# MCU.net
KiCad netlist of a schematic drawn in Altium Designer
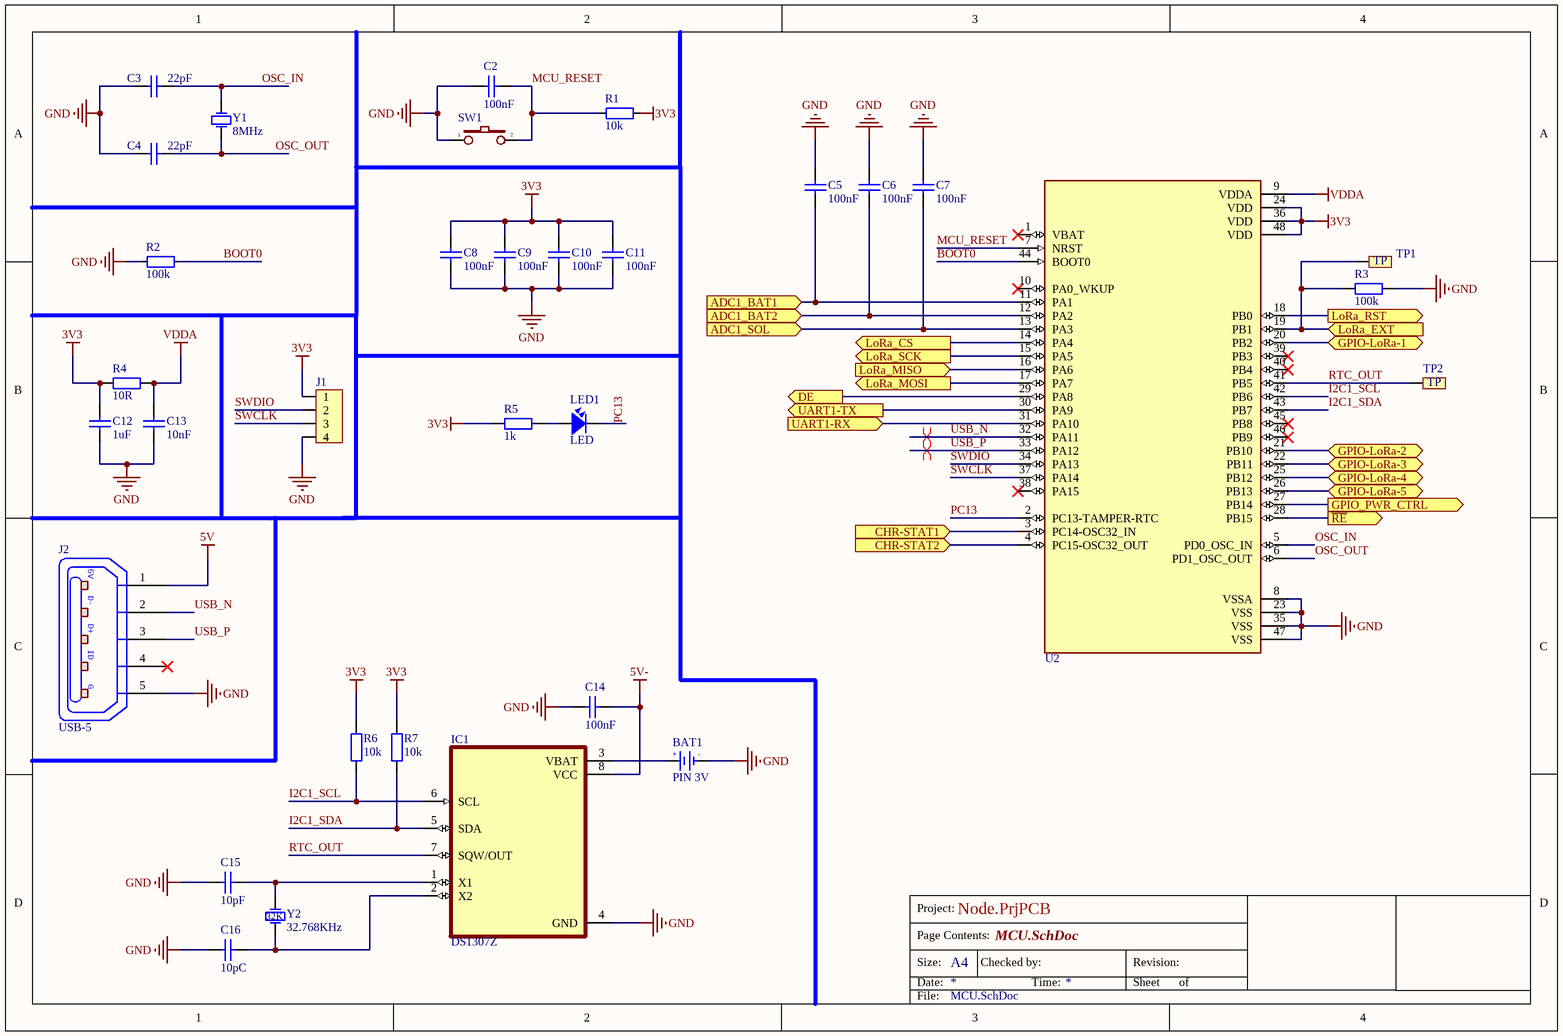
[diagram p0: MCU.SchDoc]

(export (version "E")
  (design (tool "Eeschema 10.0.6"))
  (components
    (comp (ref "BAT1")
      (value "PIN 3V")
      (footprint "CR1220 SMD")
      (description "Battery 3VDC")
      (libsource (lib "My Library") (part "PIN 3V"))
    )
    (comp (ref "C2")
      (value "100nF")
      (footprint "CAP_0805")
      (description "Capacitor")
      (fields (field (name "PUBLISHER") "Altium Limited"))
      (libsource (lib "My Library") (part "CapSMD"))
    )
    (comp (ref "C3")
      (value "22pF")
      (footprint "CAP_0805")
      (description "Capacitor")
      (fields (field (name "PUBLISHER") "Altium Limited"))
      (libsource (lib "My Library") (part "CapSMD"))
    )
    (comp (ref "C4")
      (value "22pF")
      (footprint "CAP_0805")
      (description "Capacitor")
      (fields (field (name "PUBLISHER") "Altium Limited"))
      (libsource (lib "My Library") (part "CapSMD"))
    )
    (comp (ref "C5")
      (value "100nF")
      (footprint "CAP_0805")
      (description "Capacitor")
      (fields (field (name "PUBLISHER") "Altium Limited"))
      (libsource (lib "My Library") (part "CapSMD"))
    )
    (comp (ref "C6")
      (value "100nF")
      (footprint "CAP_0805")
      (description "Capacitor")
      (fields (field (name "PUBLISHER") "Altium Limited"))
      (libsource (lib "My Library") (part "CapSMD"))
    )
    (comp (ref "C7")
      (value "100nF")
      (footprint "CAP_0805")
      (description "Capacitor")
      (fields (field (name "PUBLISHER") "Altium Limited"))
      (libsource (lib "My Library") (part "CapSMD"))
    )
    (comp (ref "C8")
      (value "100nF")
      (footprint "CAP_0805")
      (description "Capacitor")
      (fields (field (name "PUBLISHER") "Altium Limited"))
      (libsource (lib "My Library") (part "CapSMD"))
    )
    (comp (ref "C9")
      (value "100nF")
      (footprint "CAP_0805")
      (description "Capacitor")
      (fields (field (name "PUBLISHER") "Altium Limited"))
      (libsource (lib "My Library") (part "CapSMD"))
    )
    (comp (ref "C10")
      (value "100nF")
      (footprint "CAP_0805")
      (description "Capacitor")
      (fields (field (name "PUBLISHER") "Altium Limited"))
      (libsource (lib "My Library") (part "CapSMD"))
    )
    (comp (ref "C11")
      (value "100nF")
      (footprint "CAP_0805")
      (description "Capacitor")
      (fields (field (name "PUBLISHER") "Altium Limited"))
      (libsource (lib "My Library") (part "CapSMD"))
    )
    (comp (ref "C12")
      (value "1uF")
      (footprint "CAP_0805")
      (description "Capacitor")
      (fields (field (name "PUBLISHER") "Altium Limited"))
      (libsource (lib "My Library") (part "CapSMD"))
    )
    (comp (ref "C13")
      (value "10nF")
      (footprint "CAP_0805")
      (description "Capacitor")
      (fields (field (name "PUBLISHER") "Altium Limited"))
      (libsource (lib "My Library") (part "CapSMD"))
    )
    (comp (ref "C14")
      (value "100nF")
      (footprint "CAP_0805")
      (description "Capacitor")
      (fields (field (name "PUBLISHER") "Altium Limited"))
      (libsource (lib "My Library") (part "CapSMD"))
    )
    (comp (ref "C15")
      (value "10pF")
      (footprint "CAP_0805")
      (description "Capacitor")
      (fields (field (name "PUBLISHER") "Altium Limited"))
      (libsource (lib "My Library") (part "CapSMD"))
    )
    (comp (ref "C16")
      (value "10pC")
      (footprint "CAP_0805")
      (description "Capacitor")
      (fields (field (name "PUBLISHER") "Altium Limited"))
      (libsource (lib "My Library") (part "CapSMD"))
    )
    (comp (ref "IC1") (value "DS1307Z") (footprint "SOIC-8") (libsource (lib "My Library") (part "DS1307Z")))
    (comp (ref "J1")
      (value "ST_Link")
      (footprint "Jump_4p")
      (description "Header IDC, 4 x 1 Pin Vertical 2.54mm Pitch (Non-Boxed, Male)")
      (fields
        (field (name "MANUFACTURER") "Würth Elektronik eiSos GmbH")
        (field (name "PARTNO") "613002143121")
        (field (name "CREATED BY") "Karrer Zheng")
      )
      (libsource (lib "My Library") (part "Header4"))
    )
    (comp (ref "J2")
      (value "USB-5")
      (footprint "USB-M1")
      (fields
        (field (name "MANUFACTURER") "FCI")
        (field (name "MANUFACTURER PART NUMBER") "10118193-0001LF")
        (field (name ".CREATOR") "MM")
        (field (name ".CHECKED PCB") "RF")
        (field (name ".CHECKED SCH") "MM")
      )
      (libsource (lib "My Library") (part "USB-5"))
    )
    (comp (ref "LED1")
      (value "LED")
      (footprint "LED-0805-Red")
      (description "LED Single colour Green and Red")
      (libsource (lib "My Library") (part "LED"))
    )
    (comp (ref "R1")
      (value "10k")
      (footprint "RES-SMD-0805")
      (description "Resistor")
      (fields
        (field (name "MANUFACTURER") "Generic Components")
        (field (name "PUBLISHER") "Altium Hobart Technology Centre")
      )
      (libsource (lib "") (part "Resistor - SMD_1"))
    )
    (comp (ref "R2")
      (value "100k")
      (footprint "RES-SMD-0805")
      (description "Resistor")
      (fields
        (field (name "MANUFACTURER") "Generic Components")
        (field (name "PUBLISHER") "Altium Hobart Technology Centre")
      )
      (libsource (lib "") (part "Resistor - SMD_1"))
    )
    (comp (ref "R3")
      (value "100k")
      (footprint "RES-SMD-0805")
      (description "Resistor SMD")
      (fields
        (field (name "MANUFACTURER") "Generic Components")
        (field (name "PUBLISHER") "Altium Hobart Technology Centre")
      )
      (libsource (lib "My Library") (part "Resistor - SMD"))
    )
    (comp (ref "R4")
      (value "10R")
      (footprint "RES-SMD-0805")
      (description "Resistor SMD")
      (fields
        (field (name "MANUFACTURER") "Generic Components")
        (field (name "PUBLISHER") "Altium Hobart Technology Centre")
      )
      (libsource (lib "My Library") (part "Resistor - SMD"))
    )
    (comp (ref "R5")
      (value "1k")
      (footprint "RES-SMD-0805")
      (description "Resistor SMD")
      (fields
        (field (name "MANUFACTURER") "Generic Components")
        (field (name "PUBLISHER") "Altium Hobart Technology Centre")
      )
      (libsource (lib "My Library") (part "Resistor - SMD"))
    )
    (comp (ref "R6")
      (value "10k")
      (footprint "RES-SMD-0805")
      (description "Resistor SMD")
      (fields
        (field (name "MANUFACTURER") "Generic Components")
        (field (name "PUBLISHER") "Altium Hobart Technology Centre")
      )
      (libsource (lib "My Library") (part "Resistor - SMD"))
    )
    (comp (ref "R7")
      (value "10k")
      (footprint "RES-SMD-0805")
      (description "Resistor SMD")
      (fields
        (field (name "MANUFACTURER") "Generic Components")
        (field (name "PUBLISHER") "Altium Hobart Technology Centre")
      )
      (libsource (lib "My Library") (part "Resistor - SMD"))
    )
    (comp (ref "SW1")
      (value "SW")
      (footprint "SW 3x2x4")
      (description "Switch button 2 pin")
      (libsource (lib "My Library") (part "SW2"))
    )
    (comp (ref "TP1")
      (value "Test Point")
      (footprint "TP_SMD")
      (description "CONNECT 1")
      (libsource (lib "My Library") (part "TP"))
    )
    (comp (ref "TP2")
      (value "Test Point")
      (footprint "TP_SMD")
      (description "CONNECT 1")
      (libsource (lib "My Library") (part "TP"))
    )
    (comp (ref "U2")
      (value "STM32")
      (footprint "LQFP 48")
      (description "STM32 ARM-based 32-bit MCU with 64 Kbytes Flash, 64-pin LQFP, Industrial Temperature")
      (libsource (lib "Ven_lib") (part "STM32F103C8T6"))
    )
    (comp (ref "Y1")
      (value "8MHz")
      (footprint "XTAL")
      (description "Crystal Oscillator")
      (fields (field (name "PUBLISHER") "Altium Limited"))
      (libsource (lib "My Library") (part "XTAL"))
    )
    (comp (ref "Y2")
      (value "32.768KHz")
      (footprint "XTAL32K")
      (description "Crystal Oscillator")
      (fields (field (name "PUBLISHER") "Altium Limited"))
      (libsource (lib "My Library") (part "XTAL/32KHz"))
    )
  )
  (nets
    (net (code "1") (name "/ADC1_BAT1") (class "Default")
      (node (ref "C5") (pin "1") (pinfunction "1_1") (pintype "passive"))
      (node (ref "U2") (pin "11") (pinfunction "PA1_11") (pintype "bidirectional"))
    )
    (net (code "2") (name "/ADC1_BAT2") (class "Default")
      (node (ref "C6") (pin "1") (pinfunction "1_1") (pintype "passive"))
      (node (ref "U2") (pin "12") (pinfunction "PA2_12") (pintype "bidirectional"))
    )
    (net (code "3") (name "/ADC1_SOL") (class "Default")
      (node (ref "C7") (pin "1") (pinfunction "1_1") (pintype "passive"))
      (node (ref "U2") (pin "13") (pinfunction "PA3_13") (pintype "bidirectional"))
    )
    (net (code "4") (name "/BOOT0") (class "Default")
      (node (ref "R2") (pin "1") (pinfunction "1_1") (pintype "passive"))
      (node (ref "U2") (pin "44") (pinfunction "BOOT0_44") (pintype "input"))
    )
    (net (code "5") (name "/CHR-STAT1") (class "Default")
      (node (ref "U2") (pin "3") (pinfunction "PC14-OSC32_IN_3") (pintype "bidirectional"))
    )
    (net (code "6") (name "/CHR-STAT2") (class "Default")
      (node (ref "U2") (pin "4") (pinfunction "PC15-OSC32_OUT_4") (pintype "bidirectional"))
    )
    (net (code "7") (name "/DE") (class "Default")
      (node (ref "U2") (pin "29") (pinfunction "PA8_29") (pintype "bidirectional"))
    )
    (net (code "8") (name "/GPIO-LoRa-1") (class "Default")
      (node (ref "U2") (pin "20") (pinfunction "PB2_20") (pintype "bidirectional"))
    )
    (net (code "9") (name "/GPIO-LoRa-2") (class "Default")
      (node (ref "U2") (pin "21") (pinfunction "PB10_21") (pintype "bidirectional"))
    )
    (net (code "10") (name "/GPIO-LoRa-3") (class "Default")
      (node (ref "U2") (pin "22") (pinfunction "PB11_22") (pintype "bidirectional"))
    )
    (net (code "11") (name "/GPIO-LoRa-4") (class "Default")
      (node (ref "U2") (pin "25") (pinfunction "PB12_25") (pintype "bidirectional"))
    )
    (net (code "12") (name "/GPIO-LoRa-5") (class "Default")
      (node (ref "U2") (pin "26") (pinfunction "PB13_26") (pintype "bidirectional"))
    )
    (net (code "13") (name "/GPIO_PWR_CTRL") (class "Default")
      (node (ref "U2") (pin "27") (pinfunction "PB14_27") (pintype "bidirectional"))
    )
    (net (code "14") (name "/I2C1_SCL") (class "Default")
      (node (ref "IC1") (pin "6") (pinfunction "SCL_6") (pintype "input"))
      (node (ref "R6") (pin "1") (pinfunction "1_1") (pintype "passive"))
      (node (ref "U2") (pin "42") (pinfunction "PB6_42") (pintype "bidirectional"))
    )
    (net (code "15") (name "/I2C1_SDA") (class "Default")
      (node (ref "IC1") (pin "5") (pinfunction "SDA_5") (pintype "bidirectional"))
      (node (ref "R7") (pin "1") (pinfunction "1_1") (pintype "passive"))
      (node (ref "U2") (pin "43") (pinfunction "PB7_43") (pintype "bidirectional"))
    )
    (net (code "16") (name "/LoRa_CS") (class "Default")
      (node (ref "U2") (pin "14") (pinfunction "PA4_14") (pintype "bidirectional"))
    )
    (net (code "17") (name "/LoRa_EXT") (class "Default")
      (node (ref "R3") (pin "1") (pinfunction "1_1") (pintype "passive"))
      (node (ref "TP1") (pin "1") (pinfunction "0_1") (pintype "passive"))
      (node (ref "U2") (pin "19") (pinfunction "PB1_19") (pintype "bidirectional"))
    )
    (net (code "18") (name "/LoRa_MISO") (class "Default")
      (node (ref "U2") (pin "16") (pinfunction "PA6_16") (pintype "bidirectional"))
    )
    (net (code "19") (name "/LoRa_MOSI") (class "Default")
      (node (ref "U2") (pin "17") (pinfunction "PA7_17") (pintype "bidirectional"))
    )
    (net (code "20") (name "/LoRa_RST") (class "Default")
      (node (ref "U2") (pin "18") (pinfunction "PB0_18") (pintype "bidirectional"))
    )
    (net (code "21") (name "/LoRa_SCK") (class "Default")
      (node (ref "U2") (pin "15") (pinfunction "PA5_15") (pintype "bidirectional"))
    )
    (net (code "22") (name "/MCU_RESET") (class "Default")
      (node (ref "C2") (pin "2") (pinfunction "2_2") (pintype "passive"))
      (node (ref "R1") (pin "2") (pinfunction "2_2") (pintype "passive"))
      (node (ref "SW1") (pin "2") (pinfunction "2_2") (pintype "passive"))
      (node (ref "U2") (pin "7") (pinfunction "NRST_7") (pintype "input"))
    )
    (net (code "23") (name "/OSC_IN") (class "Default")
      (node (ref "C3") (pin "2") (pinfunction "2_2") (pintype "passive"))
      (node (ref "U2") (pin "5") (pinfunction "PD0_OSC_IN_5") (pintype "bidirectional"))
      (node (ref "Y1") (pin "1") (pinfunction "OSC1_1") (pintype "passive"))
    )
    (net (code "24") (name "/OSC_OUT") (class "Default")
      (node (ref "C4") (pin "2") (pinfunction "2_2") (pintype "passive"))
      (node (ref "U2") (pin "6") (pinfunction "PD1_OSC_OUT_6") (pintype "bidirectional"))
      (node (ref "Y1") (pin "2") (pinfunction "OSC2_2") (pintype "passive"))
    )
    (net (code "25") (name "/PC13") (class "Default")
      (node (ref "LED1") (pin "2") (pinfunction "2_2") (pintype "passive"))
      (node (ref "U2") (pin "2") (pinfunction "PC13-TAMPER-RTC_2") (pintype "bidirectional"))
    )
    (net (code "26") (name "/RTC_OUT") (class "Default")
      (node (ref "IC1") (pin "7") (pinfunction "SQW/OUT_7") (pintype "bidirectional"))
      (node (ref "TP2") (pin "1") (pinfunction "0_1") (pintype "passive"))
      (node (ref "U2") (pin "41") (pinfunction "PB5_41") (pintype "bidirectional"))
    )
    (net (code "27") (name "/SWCLK") (class "Default")
      (node (ref "J1") (pin "3") (pinfunction "3_3") (pintype "passive"))
      (node (ref "U2") (pin "37") (pinfunction "PA14_37") (pintype "bidirectional"))
    )
    (net (code "28") (name "/SWDIO") (class "Default")
      (node (ref "J1") (pin "2") (pinfunction "2_2") (pintype "passive"))
      (node (ref "U2") (pin "34") (pinfunction "PA13_34") (pintype "bidirectional"))
    )
    (net (code "29") (name "/UART1-RX") (class "Default")
      (node (ref "U2") (pin "31") (pinfunction "PA10_31") (pintype "bidirectional"))
    )
    (net (code "30") (name "/UART1-TX") (class "Default")
      (node (ref "U2") (pin "30") (pinfunction "PA9_30") (pintype "bidirectional"))
    )
    (net (code "31") (name "/USB_N") (class "Default")
      (node (ref "J2") (pin "2") (pinfunction "P2_2") (pintype "passive"))
      (node (ref "U2") (pin "32") (pinfunction "PA11_32") (pintype "bidirectional"))
    )
    (net (code "32") (name "/USB_P") (class "Default")
      (node (ref "J2") (pin "3") (pinfunction "P3_3") (pintype "passive"))
      (node (ref "U2") (pin "33") (pinfunction "PA12_33") (pintype "bidirectional"))
    )
    (net (code "33") (name "/~{RE}") (class "Default")
      (node (ref "U2") (pin "28") (pinfunction "PB15_28") (pintype "bidirectional"))
    )
    (net (code "34") (name "3V3") (class "Default")
      (node (ref "C10") (pin "2") (pinfunction "2_2") (pintype "passive"))
      (node (ref "C11") (pin "2") (pinfunction "2_2") (pintype "passive"))
      (node (ref "C12") (pin "2") (pinfunction "2_2") (pintype "passive"))
      (node (ref "C8") (pin "2") (pinfunction "2_2") (pintype "passive"))
      (node (ref "C9") (pin "2") (pinfunction "2_2") (pintype "passive"))
      (node (ref "J1") (pin "1") (pinfunction "1_1") (pintype "passive"))
      (node (ref "R1") (pin "1") (pinfunction "1_1") (pintype "passive"))
      (node (ref "R4") (pin "1") (pinfunction "1_1") (pintype "passive"))
      (node (ref "R5") (pin "1") (pinfunction "1_1") (pintype "passive"))
      (node (ref "R6") (pin "2") (pinfunction "2_2") (pintype "passive"))
      (node (ref "R7") (pin "2") (pinfunction "2_2") (pintype "passive"))
      (node (ref "U2") (pin "24") (pinfunction "VDD_24") (pintype "power_in"))
      (node (ref "U2") (pin "36") (pinfunction "VDD_36") (pintype "power_in"))
      (node (ref "U2") (pin "48") (pinfunction "VDD_48") (pintype "power_in"))
    )
    (net (code "35") (name "5V") (class "Default")
      (node (ref "J2") (pin "1") (pinfunction "P1_1") (pintype "passive"))
    )
    (net (code "36") (name "5V-") (class "Default")
      (node (ref "C14") (pin "2") (pinfunction "2_2") (pintype "passive"))
      (node (ref "IC1") (pin "8") (pinfunction "VCC_8") (pintype "power_in"))
    )
    (net (code "37") (name "GND") (class "Default")
      (node (ref "BAT1") (pin "2") (pinfunction "GND_2") (pintype "passive"))
      (node (ref "C10") (pin "1") (pinfunction "1_1") (pintype "passive"))
      (node (ref "C11") (pin "1") (pinfunction "1_1") (pintype "passive"))
      (node (ref "C12") (pin "1") (pinfunction "1_1") (pintype "passive"))
      (node (ref "C13") (pin "1") (pinfunction "1_1") (pintype "passive"))
      (node (ref "C14") (pin "1") (pinfunction "1_1") (pintype "passive"))
      (node (ref "C15") (pin "2") (pinfunction "2_2") (pintype "passive"))
      (node (ref "C16") (pin "2") (pinfunction "2_2") (pintype "passive"))
      (node (ref "C2") (pin "1") (pinfunction "1_1") (pintype "passive"))
      (node (ref "C3") (pin "1") (pinfunction "1_1") (pintype "passive"))
      (node (ref "C4") (pin "1") (pinfunction "1_1") (pintype "passive"))
      (node (ref "C5") (pin "2") (pinfunction "2_2") (pintype "passive"))
      (node (ref "C6") (pin "2") (pinfunction "2_2") (pintype "passive"))
      (node (ref "C7") (pin "2") (pinfunction "2_2") (pintype "passive"))
      (node (ref "C8") (pin "1") (pinfunction "1_1") (pintype "passive"))
      (node (ref "C9") (pin "1") (pinfunction "1_1") (pintype "passive"))
      (node (ref "IC1") (pin "4") (pinfunction "GND_4") (pintype "power_in"))
      (node (ref "J1") (pin "4") (pinfunction "4_4") (pintype "passive"))
      (node (ref "J2") (pin "5") (pinfunction "P5_5") (pintype "passive"))
      (node (ref "R2") (pin "2") (pinfunction "2_2") (pintype "passive"))
      (node (ref "R3") (pin "2") (pinfunction "2_2") (pintype "passive"))
      (node (ref "SW1") (pin "1") (pinfunction "1_1") (pintype "passive"))
      (node (ref "U2") (pin "23") (pinfunction "VSS_23") (pintype "power_in"))
      (node (ref "U2") (pin "35") (pinfunction "VSS_35") (pintype "power_in"))
      (node (ref "U2") (pin "47") (pinfunction "VSS_47") (pintype "power_in"))
      (node (ref "U2") (pin "8") (pinfunction "VSSA_8") (pintype "power_in"))
    )
    (net (code "38") (name "Net-(BAT1-+3V)") (class "Default")
      (node (ref "BAT1") (pin "1") (pinfunction "+3V_1") (pintype "passive"))
      (node (ref "IC1") (pin "3") (pinfunction "VBAT_3") (pintype "power_in"))
    )
    (net (code "39") (name "Net-(IC1-X1)") (class "Default")
      (node (ref "C15") (pin "1") (pinfunction "1_1") (pintype "passive"))
      (node (ref "IC1") (pin "1") (pinfunction "X1_1") (pintype "bidirectional"))
      (node (ref "Y2") (pin "1") (pinfunction "OSC1_1") (pintype "passive"))
    )
    (net (code "40") (name "Net-(IC1-X2)") (class "Default")
      (node (ref "C16") (pin "1") (pinfunction "1_1") (pintype "passive"))
      (node (ref "IC1") (pin "2") (pinfunction "X2_2") (pintype "bidirectional"))
      (node (ref "Y2") (pin "2") (pinfunction "OSC2_2") (pintype "passive"))
    )
    (net (code "41") (name "Net-(LED1-Pad1)") (class "Default")
      (node (ref "LED1") (pin "1") (pinfunction "1_1") (pintype "passive"))
      (node (ref "R5") (pin "2") (pinfunction "2_2") (pintype "passive"))
    )
    (net (code "42") (name "VDDA") (class "Default")
      (node (ref "C13") (pin "2") (pinfunction "2_2") (pintype "passive"))
      (node (ref "R4") (pin "2") (pinfunction "2_2") (pintype "passive"))
      (node (ref "U2") (pin "9") (pinfunction "VDDA_9") (pintype "power_in"))
    )
    (net (code "43") (name "unconnected-(J2-P4-Pad4)") (class "Default")
      (node (ref "J2") (pin "4") (pinfunction "P4_4") (pintype "passive+no_connect"))
    )
    (net (code "44") (name "unconnected-(U2-PA0_WKUP-Pad10)") (class "Default")
      (node (ref "U2") (pin "10") (pinfunction "PA0_WKUP_10") (pintype "bidirectional+no_connect"))
    )
    (net (code "45") (name "unconnected-(U2-PA15-Pad38)") (class "Default")
      (node (ref "U2") (pin "38") (pinfunction "PA15_38") (pintype "bidirectional+no_connect"))
    )
    (net (code "46") (name "unconnected-(U2-PB3-Pad39)") (class "Default")
      (node (ref "U2") (pin "39") (pinfunction "PB3_39") (pintype "bidirectional+no_connect"))
    )
    (net (code "47") (name "unconnected-(U2-PB4-Pad40)") (class "Default")
      (node (ref "U2") (pin "40") (pinfunction "PB4_40") (pintype "bidirectional+no_connect"))
    )
    (net (code "48") (name "unconnected-(U2-PB8-Pad45)") (class "Default")
      (node (ref "U2") (pin "45") (pinfunction "PB8_45") (pintype "bidirectional+no_connect"))
    )
    (net (code "49") (name "unconnected-(U2-PB9-Pad46)") (class "Default")
      (node (ref "U2") (pin "46") (pinfunction "PB9_46") (pintype "bidirectional+no_connect"))
    )
    (net (code "50") (name "unconnected-(U2-VBAT-Pad1)") (class "Default")
      (node (ref "U2") (pin "1") (pinfunction "VBAT_1") (pintype "bidirectional+no_connect"))
    )
  )
)
